# TestBoard2.net
KiCad netlist of a schematic drawn in EAGLE
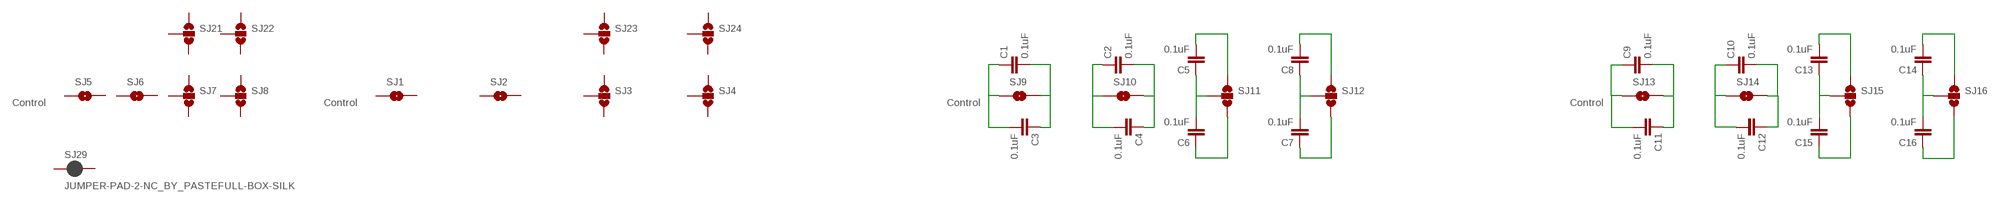
[diagram p0: schematic, sheet 1, part 1 of 3]
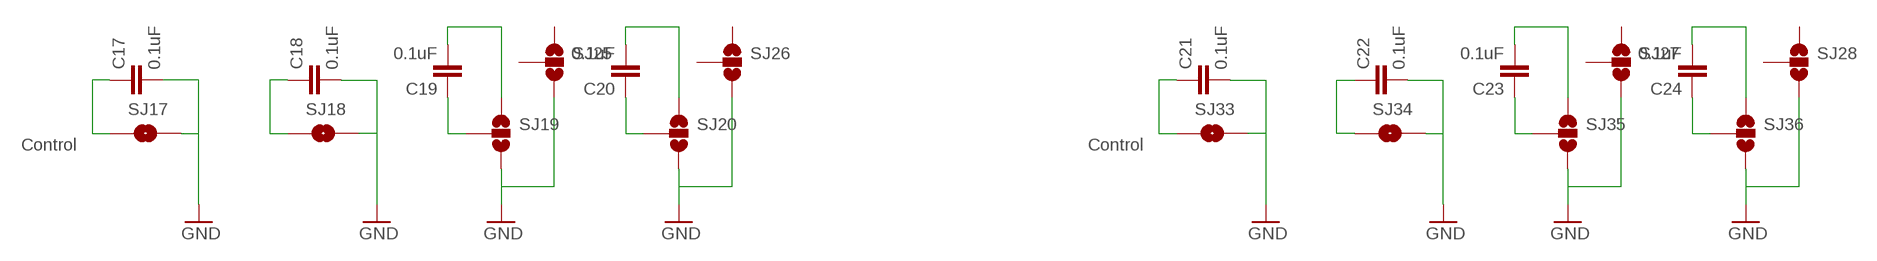
[diagram p1: schematic, sheet 1, part 2 of 3]
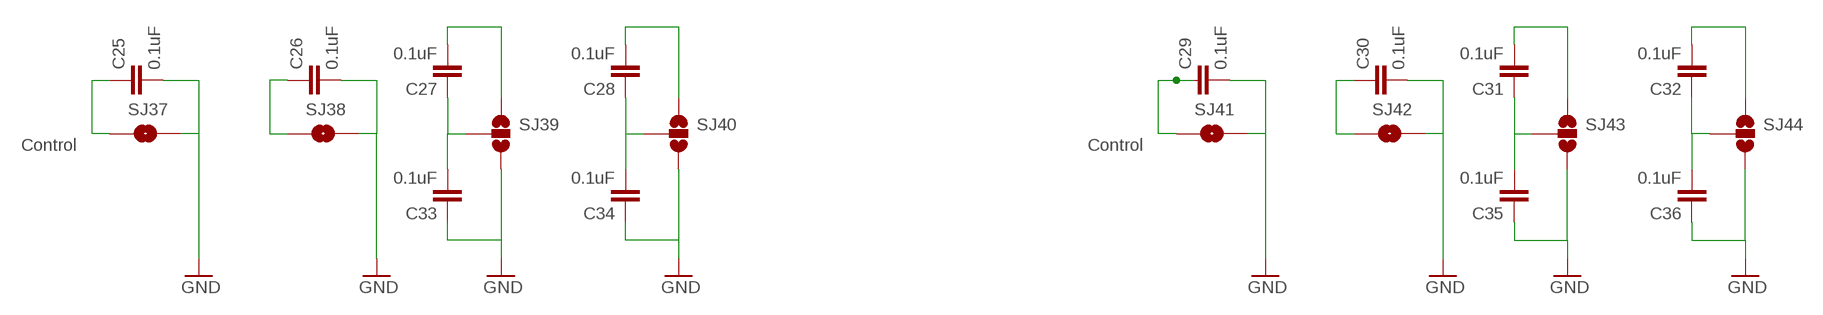
[diagram p2: schematic, sheet 1, part 3 of 3]

(export (version "E")
  (design (tool "Eeschema 10.0.6"))
  (components
    (comp (ref "C1")
      (value "0.1uF")
      (footprint "eagle-import:0603-CAP")
      (libsource (lib "eagle-import") (part "0.1UF-25V-5%(0603)"))
    )
    (comp (ref "C2")
      (value "0.1uF")
      (footprint "eagle-import:0603-CAP")
      (libsource (lib "eagle-import") (part "0.1UF-25V-5%(0603)"))
    )
    (comp (ref "C3")
      (value "0.1uF")
      (footprint "eagle-import:0603-CAP")
      (libsource (lib "eagle-import") (part "0.1UF-25V-5%(0603)"))
    )
    (comp (ref "C4")
      (value "0.1uF")
      (footprint "eagle-import:0603-CAP")
      (libsource (lib "eagle-import") (part "0.1UF-25V-5%(0603)"))
    )
    (comp (ref "C5")
      (value "0.1uF")
      (footprint "eagle-import:0603-CAP")
      (libsource (lib "eagle-import") (part "0.1UF-25V-5%(0603)"))
    )
    (comp (ref "C6")
      (value "0.1uF")
      (footprint "eagle-import:0603-CAP")
      (libsource (lib "eagle-import") (part "0.1UF-25V-5%(0603)"))
    )
    (comp (ref "C7")
      (value "0.1uF")
      (footprint "eagle-import:0603-CAP")
      (libsource (lib "eagle-import") (part "0.1UF-25V-5%(0603)"))
    )
    (comp (ref "C8")
      (value "0.1uF")
      (footprint "eagle-import:0603-CAP")
      (libsource (lib "eagle-import") (part "0.1UF-25V-5%(0603)"))
    )
    (comp (ref "C9")
      (value "0.1uF")
      (footprint "eagle-import:0603-CAP")
      (libsource (lib "eagle-import") (part "0.1UF-25V-5%(0603)"))
    )
    (comp (ref "C10")
      (value "0.1uF")
      (footprint "eagle-import:0603-CAP")
      (libsource (lib "eagle-import") (part "0.1UF-25V-5%(0603)"))
    )
    (comp (ref "C11")
      (value "0.1uF")
      (footprint "eagle-import:0603-CAP")
      (libsource (lib "eagle-import") (part "0.1UF-25V-5%(0603)"))
    )
    (comp (ref "C12")
      (value "0.1uF")
      (footprint "eagle-import:0603-CAP")
      (libsource (lib "eagle-import") (part "0.1UF-25V-5%(0603)"))
    )
    (comp (ref "C13")
      (value "0.1uF")
      (footprint "eagle-import:0603-CAP")
      (libsource (lib "eagle-import") (part "0.1UF-25V-5%(0603)"))
    )
    (comp (ref "C14")
      (value "0.1uF")
      (footprint "eagle-import:0603-CAP")
      (libsource (lib "eagle-import") (part "0.1UF-25V-5%(0603)"))
    )
    (comp (ref "C15")
      (value "0.1uF")
      (footprint "eagle-import:0603-CAP")
      (libsource (lib "eagle-import") (part "0.1UF-25V-5%(0603)"))
    )
    (comp (ref "C16")
      (value "0.1uF")
      (footprint "eagle-import:0603-CAP")
      (libsource (lib "eagle-import") (part "0.1UF-25V-5%(0603)"))
    )
    (comp (ref "C17")
      (value "0.1uF")
      (footprint "eagle-import:0603-CAP")
      (libsource (lib "eagle-import") (part "0.1UF-25V-5%(0603)"))
    )
    (comp (ref "C18")
      (value "0.1uF")
      (footprint "eagle-import:0603-CAP")
      (libsource (lib "eagle-import") (part "0.1UF-25V-5%(0603)"))
    )
    (comp (ref "C19")
      (value "0.1uF")
      (footprint "eagle-import:0603-CAP")
      (libsource (lib "eagle-import") (part "0.1UF-25V-5%(0603)"))
    )
    (comp (ref "C20")
      (value "0.1uF")
      (footprint "eagle-import:0603-CAP")
      (libsource (lib "eagle-import") (part "0.1UF-25V-5%(0603)"))
    )
    (comp (ref "C21")
      (value "0.1uF")
      (footprint "eagle-import:0603-CAP")
      (libsource (lib "eagle-import") (part "0.1UF-25V-5%(0603)"))
    )
    (comp (ref "C22")
      (value "0.1uF")
      (footprint "eagle-import:0603-CAP")
      (libsource (lib "eagle-import") (part "0.1UF-25V-5%(0603)"))
    )
    (comp (ref "C23")
      (value "0.1uF")
      (footprint "eagle-import:0603-CAP")
      (libsource (lib "eagle-import") (part "0.1UF-25V-5%(0603)"))
    )
    (comp (ref "C24")
      (value "0.1uF")
      (footprint "eagle-import:0603-CAP")
      (libsource (lib "eagle-import") (part "0.1UF-25V-5%(0603)"))
    )
    (comp (ref "C25")
      (value "0.1uF")
      (footprint "eagle-import:0603-CAP")
      (libsource (lib "eagle-import") (part "0.1UF-25V-5%(0603)"))
    )
    (comp (ref "C26")
      (value "0.1uF")
      (footprint "eagle-import:0603-CAP")
      (libsource (lib "eagle-import") (part "0.1UF-25V-5%(0603)"))
    )
    (comp (ref "C27")
      (value "0.1uF")
      (footprint "eagle-import:0603-CAP")
      (libsource (lib "eagle-import") (part "0.1UF-25V-5%(0603)"))
    )
    (comp (ref "C28")
      (value "0.1uF")
      (footprint "eagle-import:0603-CAP")
      (libsource (lib "eagle-import") (part "0.1UF-25V-5%(0603)"))
    )
    (comp (ref "C29")
      (value "0.1uF")
      (footprint "eagle-import:0603-CAP")
      (libsource (lib "eagle-import") (part "0.1UF-25V-5%(0603)"))
    )
    (comp (ref "C30")
      (value "0.1uF")
      (footprint "eagle-import:0603-CAP")
      (libsource (lib "eagle-import") (part "0.1UF-25V-5%(0603)"))
    )
    (comp (ref "C31")
      (value "0.1uF")
      (footprint "eagle-import:0603-CAP")
      (libsource (lib "eagle-import") (part "0.1UF-25V-5%(0603)"))
    )
    (comp (ref "C32")
      (value "0.1uF")
      (footprint "eagle-import:0603-CAP")
      (libsource (lib "eagle-import") (part "0.1UF-25V-5%(0603)"))
    )
    (comp (ref "C33")
      (value "0.1uF")
      (footprint "eagle-import:0603-CAP")
      (libsource (lib "eagle-import") (part "0.1UF-25V-5%(0603)"))
    )
    (comp (ref "C34")
      (value "0.1uF")
      (footprint "eagle-import:0603-CAP")
      (libsource (lib "eagle-import") (part "0.1UF-25V-5%(0603)"))
    )
    (comp (ref "C35")
      (value "0.1uF")
      (footprint "eagle-import:0603-CAP")
      (libsource (lib "eagle-import") (part "0.1UF-25V-5%(0603)"))
    )
    (comp (ref "C36")
      (value "0.1uF")
      (footprint "eagle-import:0603-CAP")
      (libsource (lib "eagle-import") (part "0.1UF-25V-5%(0603)"))
    )
    (comp (ref "SJ1")
      (value "JUMPER-PAD-2-NO")
      (footprint "eagle-import:PAD-JUMPER-2-NO_NO_SILK")
      (libsource (lib "eagle-import") (part "JUMPER-PAD-2-NO"))
    )
    (comp (ref "SJ2")
      (value "JUMPER-PAD-2-NO")
      (footprint "eagle-import:PAD-JUMPER-2-NO_NO_SILK")
      (libsource (lib "eagle-import") (part "JUMPER-PAD-2-NO"))
    )
    (comp (ref "SJ3")
      (value "JUMPER-PAD-3-NOYES_SILK")
      (footprint "eagle-import:PAD-JUMPER-3-NO_YES_SILK")
      (libsource (lib "eagle-import") (part "JUMPER-PAD-3-NOYES_SILK"))
    )
    (comp (ref "SJ4")
      (value "JUMPER-PAD-3-NOYES_SILK")
      (footprint "eagle-import:PAD-JUMPER-3-NO_YES_SILK")
      (libsource (lib "eagle-import") (part "JUMPER-PAD-3-NOYES_SILK"))
    )
    (comp (ref "SJ5")
      (value "JUMPER-PAD-2-NO")
      (footprint "eagle-import:PAD-JUMPER-2-NO_NO_SILK")
      (libsource (lib "eagle-import") (part "JUMPER-PAD-2-NO"))
    )
    (comp (ref "SJ6")
      (value "JUMPER-PAD-2-NO")
      (footprint "eagle-import:PAD-JUMPER-2-NO_NO_SILK")
      (libsource (lib "eagle-import") (part "JUMPER-PAD-2-NO"))
    )
    (comp (ref "SJ7")
      (value "JUMPER-PAD-3-NOYES_SILK")
      (footprint "eagle-import:PAD-JUMPER-3-NO_YES_SILK")
      (libsource (lib "eagle-import") (part "JUMPER-PAD-3-NOYES_SILK"))
    )
    (comp (ref "SJ8")
      (value "JUMPER-PAD-3-NOYES_SILK")
      (footprint "eagle-import:PAD-JUMPER-3-NO_YES_SILK")
      (libsource (lib "eagle-import") (part "JUMPER-PAD-3-NOYES_SILK"))
    )
    (comp (ref "SJ9")
      (value "JUMPER-PAD-2-NO")
      (footprint "eagle-import:PAD-JUMPER-2-NO_NO_SILK")
      (libsource (lib "eagle-import") (part "JUMPER-PAD-2-NO"))
    )
    (comp (ref "SJ10")
      (value "JUMPER-PAD-2-NO")
      (footprint "eagle-import:PAD-JUMPER-2-NO_NO_SILK")
      (libsource (lib "eagle-import") (part "JUMPER-PAD-2-NO"))
    )
    (comp (ref "SJ11")
      (value "JUMPER-PAD-3-NOYES_SILK")
      (footprint "eagle-import:PAD-JUMPER-3-NO_YES_SILK")
      (libsource (lib "eagle-import") (part "JUMPER-PAD-3-NOYES_SILK"))
    )
    (comp (ref "SJ12")
      (value "JUMPER-PAD-3-NOYES_SILK")
      (footprint "eagle-import:PAD-JUMPER-3-NO_YES_SILK")
      (libsource (lib "eagle-import") (part "JUMPER-PAD-3-NOYES_SILK"))
    )
    (comp (ref "SJ13")
      (value "JUMPER-PAD-2-NO")
      (footprint "eagle-import:PAD-JUMPER-2-NO_NO_SILK")
      (libsource (lib "eagle-import") (part "JUMPER-PAD-2-NO"))
    )
    (comp (ref "SJ14")
      (value "JUMPER-PAD-2-NO")
      (footprint "eagle-import:PAD-JUMPER-2-NO_NO_SILK")
      (libsource (lib "eagle-import") (part "JUMPER-PAD-2-NO"))
    )
    (comp (ref "SJ15")
      (value "JUMPER-PAD-3-NOYES_SILK")
      (footprint "eagle-import:PAD-JUMPER-3-NO_YES_SILK")
      (libsource (lib "eagle-import") (part "JUMPER-PAD-3-NOYES_SILK"))
    )
    (comp (ref "SJ16")
      (value "JUMPER-PAD-3-NOYES_SILK")
      (footprint "eagle-import:PAD-JUMPER-3-NO_YES_SILK")
      (libsource (lib "eagle-import") (part "JUMPER-PAD-3-NOYES_SILK"))
    )
    (comp (ref "SJ17")
      (value "JUMPER-PAD-2-NO")
      (footprint "eagle-import:PAD-JUMPER-2-NO_NO_SILK")
      (libsource (lib "eagle-import") (part "JUMPER-PAD-2-NO"))
    )
    (comp (ref "SJ18")
      (value "JUMPER-PAD-2-NO")
      (footprint "eagle-import:PAD-JUMPER-2-NO_NO_SILK")
      (libsource (lib "eagle-import") (part "JUMPER-PAD-2-NO"))
    )
    (comp (ref "SJ19")
      (value "JUMPER-PAD-3-NOYES_SILK")
      (footprint "eagle-import:PAD-JUMPER-3-NO_YES_SILK")
      (libsource (lib "eagle-import") (part "JUMPER-PAD-3-NOYES_SILK"))
    )
    (comp (ref "SJ20")
      (value "JUMPER-PAD-3-NOYES_SILK")
      (footprint "eagle-import:PAD-JUMPER-3-NO_YES_SILK")
      (libsource (lib "eagle-import") (part "JUMPER-PAD-3-NOYES_SILK"))
    )
    (comp (ref "SJ21")
      (value "JUMPER-PAD-3-NOYES_SILK")
      (footprint "eagle-import:PAD-JUMPER-3-NO_YES_SILK")
      (libsource (lib "eagle-import") (part "JUMPER-PAD-3-NOYES_SILK"))
    )
    (comp (ref "SJ22")
      (value "JUMPER-PAD-3-NOYES_SILK")
      (footprint "eagle-import:PAD-JUMPER-3-NO_YES_SILK")
      (libsource (lib "eagle-import") (part "JUMPER-PAD-3-NOYES_SILK"))
    )
    (comp (ref "SJ23")
      (value "JUMPER-PAD-3-NOYES_SILK")
      (footprint "eagle-import:PAD-JUMPER-3-NO_YES_SILK")
      (libsource (lib "eagle-import") (part "JUMPER-PAD-3-NOYES_SILK"))
    )
    (comp (ref "SJ24")
      (value "JUMPER-PAD-3-NOYES_SILK")
      (footprint "eagle-import:PAD-JUMPER-3-NO_YES_SILK")
      (libsource (lib "eagle-import") (part "JUMPER-PAD-3-NOYES_SILK"))
    )
    (comp (ref "SJ25")
      (value "JUMPER-PAD-3-NOYES_SILK")
      (footprint "eagle-import:PAD-JUMPER-3-NO_YES_SILK")
      (libsource (lib "eagle-import") (part "JUMPER-PAD-3-NOYES_SILK"))
    )
    (comp (ref "SJ26")
      (value "JUMPER-PAD-3-NOYES_SILK")
      (footprint "eagle-import:PAD-JUMPER-3-NO_YES_SILK")
      (libsource (lib "eagle-import") (part "JUMPER-PAD-3-NOYES_SILK"))
    )
    (comp (ref "SJ27")
      (value "JUMPER-PAD-3-NOYES_SILK")
      (footprint "eagle-import:PAD-JUMPER-3-NO_YES_SILK")
      (libsource (lib "eagle-import") (part "JUMPER-PAD-3-NOYES_SILK"))
    )
    (comp (ref "SJ28")
      (value "JUMPER-PAD-3-NOYES_SILK")
      (footprint "eagle-import:PAD-JUMPER-3-NO_YES_SILK")
      (libsource (lib "eagle-import") (part "JUMPER-PAD-3-NOYES_SILK"))
    )
    (comp (ref "SJ29")
      (value "JUMPER-PAD-2-NC_BY_PASTEFULL-BOX-SILK")
      (footprint "eagle-import:PAD-JUMPER-2-NC_BY_PASTE_YES_SILK_FULL_BOX")
      (libsource (lib "eagle-import") (part "JUMPER-PAD-2-NC_BY_PASTEFULL-BOX-SILK"))
    )
    (comp (ref "SJ33")
      (value "JUMPER-PAD-2-NO")
      (footprint "eagle-import:PAD-JUMPER-2-NO_NO_SILK")
      (libsource (lib "eagle-import") (part "JUMPER-PAD-2-NO"))
    )
    (comp (ref "SJ34")
      (value "JUMPER-PAD-2-NO")
      (footprint "eagle-import:PAD-JUMPER-2-NO_NO_SILK")
      (libsource (lib "eagle-import") (part "JUMPER-PAD-2-NO"))
    )
    (comp (ref "SJ35")
      (value "JUMPER-PAD-3-NOYES_SILK")
      (footprint "eagle-import:PAD-JUMPER-3-NO_YES_SILK")
      (libsource (lib "eagle-import") (part "JUMPER-PAD-3-NOYES_SILK"))
    )
    (comp (ref "SJ36")
      (value "JUMPER-PAD-3-NOYES_SILK")
      (footprint "eagle-import:PAD-JUMPER-3-NO_YES_SILK")
      (libsource (lib "eagle-import") (part "JUMPER-PAD-3-NOYES_SILK"))
    )
    (comp (ref "SJ37")
      (value "JUMPER-PAD-2-NO")
      (footprint "eagle-import:PAD-JUMPER-2-NO_NO_SILK")
      (libsource (lib "eagle-import") (part "JUMPER-PAD-2-NO"))
    )
    (comp (ref "SJ38")
      (value "JUMPER-PAD-2-NO")
      (footprint "eagle-import:PAD-JUMPER-2-NO_NO_SILK")
      (libsource (lib "eagle-import") (part "JUMPER-PAD-2-NO"))
    )
    (comp (ref "SJ39")
      (value "JUMPER-PAD-3-NOYES_SILK")
      (footprint "eagle-import:PAD-JUMPER-3-NO_YES_SILK")
      (libsource (lib "eagle-import") (part "JUMPER-PAD-3-NOYES_SILK"))
    )
    (comp (ref "SJ40")
      (value "JUMPER-PAD-3-NOYES_SILK")
      (footprint "eagle-import:PAD-JUMPER-3-NO_YES_SILK")
      (libsource (lib "eagle-import") (part "JUMPER-PAD-3-NOYES_SILK"))
    )
    (comp (ref "SJ41")
      (value "JUMPER-PAD-2-NO")
      (footprint "eagle-import:PAD-JUMPER-2-NO_NO_SILK")
      (libsource (lib "eagle-import") (part "JUMPER-PAD-2-NO"))
    )
    (comp (ref "SJ42")
      (value "JUMPER-PAD-2-NO")
      (footprint "eagle-import:PAD-JUMPER-2-NO_NO_SILK")
      (libsource (lib "eagle-import") (part "JUMPER-PAD-2-NO"))
    )
    (comp (ref "SJ43")
      (value "JUMPER-PAD-3-NOYES_SILK")
      (footprint "eagle-import:PAD-JUMPER-3-NO_YES_SILK")
      (libsource (lib "eagle-import") (part "JUMPER-PAD-3-NOYES_SILK"))
    )
    (comp (ref "SJ44")
      (value "JUMPER-PAD-3-NOYES_SILK")
      (footprint "eagle-import:PAD-JUMPER-3-NO_YES_SILK")
      (libsource (lib "eagle-import") (part "JUMPER-PAD-3-NOYES_SILK"))
    )
  )
  (nets
    (net (code "1") (name "GND") (class "Default")
      (node (ref "C17") (pin "2") (pinfunction "2_2") (pintype "passive"))
      (node (ref "C18") (pin "2") (pinfunction "2_2") (pintype "passive"))
      (node (ref "C21") (pin "2") (pinfunction "2_2") (pintype "passive"))
      (node (ref "C22") (pin "2") (pinfunction "2_2") (pintype "passive"))
      (node (ref "C25") (pin "2") (pinfunction "2_2") (pintype "passive"))
      (node (ref "C26") (pin "2") (pinfunction "2_2") (pintype "passive"))
      (node (ref "C29") (pin "2") (pinfunction "2_2") (pintype "passive"))
      (node (ref "C30") (pin "2") (pinfunction "2_2") (pintype "passive"))
      (node (ref "C33") (pin "1") (pinfunction "1_1") (pintype "passive"))
      (node (ref "C34") (pin "1") (pinfunction "1_1") (pintype "passive"))
      (node (ref "C35") (pin "1") (pinfunction "1_1") (pintype "passive"))
      (node (ref "C36") (pin "1") (pinfunction "1_1") (pintype "passive"))
      (node (ref "SJ17") (pin "2") (pinfunction "2_2") (pintype "passive"))
      (node (ref "SJ18") (pin "2") (pinfunction "2_2") (pintype "passive"))
      (node (ref "SJ19") (pin "3") (pinfunction "3_3") (pintype "passive"))
      (node (ref "SJ20") (pin "3") (pinfunction "3_3") (pintype "passive"))
      (node (ref "SJ25") (pin "3") (pinfunction "3_3") (pintype "passive"))
      (node (ref "SJ26") (pin "3") (pinfunction "3_3") (pintype "passive"))
      (node (ref "SJ27") (pin "3") (pinfunction "3_3") (pintype "passive"))
      (node (ref "SJ28") (pin "3") (pinfunction "3_3") (pintype "passive"))
      (node (ref "SJ33") (pin "2") (pinfunction "2_2") (pintype "passive"))
      (node (ref "SJ34") (pin "2") (pinfunction "2_2") (pintype "passive"))
      (node (ref "SJ35") (pin "3") (pinfunction "3_3") (pintype "passive"))
      (node (ref "SJ36") (pin "3") (pinfunction "3_3") (pintype "passive"))
      (node (ref "SJ37") (pin "2") (pinfunction "2_2") (pintype "passive"))
      (node (ref "SJ38") (pin "2") (pinfunction "2_2") (pintype "passive"))
      (node (ref "SJ39") (pin "3") (pinfunction "3_3") (pintype "passive"))
      (node (ref "SJ40") (pin "3") (pinfunction "3_3") (pintype "passive"))
      (node (ref "SJ41") (pin "2") (pinfunction "2_2") (pintype "passive"))
      (node (ref "SJ42") (pin "2") (pinfunction "2_2") (pintype "passive"))
      (node (ref "SJ43") (pin "3") (pinfunction "3_3") (pintype "passive"))
      (node (ref "SJ44") (pin "3") (pinfunction "3_3") (pintype "passive"))
    )
    (net (code "2") (name "Net-(C1-Pad1)") (class "Default")
      (node (ref "C1") (pin "1") (pinfunction "1_1") (pintype "passive"))
      (node (ref "C3") (pin "2") (pinfunction "2_2") (pintype "passive"))
      (node (ref "SJ9") (pin "1") (pinfunction "1_1") (pintype "passive"))
    )
    (net (code "3") (name "Net-(C1-Pad2)") (class "Default")
      (node (ref "C1") (pin "2") (pinfunction "2_2") (pintype "passive"))
      (node (ref "C3") (pin "1") (pinfunction "1_1") (pintype "passive"))
      (node (ref "SJ9") (pin "2") (pinfunction "2_2") (pintype "passive"))
    )
    (net (code "4") (name "Net-(C2-Pad1)") (class "Default")
      (node (ref "C2") (pin "1") (pinfunction "1_1") (pintype "passive"))
      (node (ref "C4") (pin "2") (pinfunction "2_2") (pintype "passive"))
      (node (ref "SJ10") (pin "1") (pinfunction "1_1") (pintype "passive"))
    )
    (net (code "5") (name "Net-(C2-Pad2)") (class "Default")
      (node (ref "C2") (pin "2") (pinfunction "2_2") (pintype "passive"))
      (node (ref "C4") (pin "1") (pinfunction "1_1") (pintype "passive"))
      (node (ref "SJ10") (pin "2") (pinfunction "2_2") (pintype "passive"))
    )
    (net (code "6") (name "Net-(C5-Pad1)") (class "Default")
      (node (ref "C5") (pin "1") (pinfunction "1_1") (pintype "passive"))
      (node (ref "C6") (pin "2") (pinfunction "2_2") (pintype "passive"))
      (node (ref "SJ11") (pin "2") (pinfunction "2_2") (pintype "passive"))
    )
    (net (code "7") (name "Net-(C5-Pad2)") (class "Default")
      (node (ref "C5") (pin "2") (pinfunction "2_2") (pintype "passive"))
      (node (ref "SJ11") (pin "1") (pinfunction "1_1") (pintype "passive"))
    )
    (net (code "8") (name "Net-(C6-Pad1)") (class "Default")
      (node (ref "C6") (pin "1") (pinfunction "1_1") (pintype "passive"))
      (node (ref "SJ11") (pin "3") (pinfunction "3_3") (pintype "passive"))
    )
    (net (code "9") (name "Net-(C7-Pad1)") (class "Default")
      (node (ref "C7") (pin "1") (pinfunction "1_1") (pintype "passive"))
      (node (ref "SJ12") (pin "3") (pinfunction "3_3") (pintype "passive"))
    )
    (net (code "10") (name "Net-(C7-Pad2)") (class "Default")
      (node (ref "C7") (pin "2") (pinfunction "2_2") (pintype "passive"))
      (node (ref "C8") (pin "1") (pinfunction "1_1") (pintype "passive"))
      (node (ref "SJ12") (pin "2") (pinfunction "2_2") (pintype "passive"))
    )
    (net (code "11") (name "Net-(C8-Pad2)") (class "Default")
      (node (ref "C8") (pin "2") (pinfunction "2_2") (pintype "passive"))
      (node (ref "SJ12") (pin "1") (pinfunction "1_1") (pintype "passive"))
    )
    (net (code "12") (name "Net-(C10-Pad1)") (class "Default")
      (node (ref "C10") (pin "1") (pinfunction "1_1") (pintype "passive"))
      (node (ref "C12") (pin "2") (pinfunction "2_2") (pintype "passive"))
      (node (ref "SJ14") (pin "1") (pinfunction "1_1") (pintype "passive"))
    )
    (net (code "13") (name "Net-(C10-Pad2)") (class "Default")
      (node (ref "C10") (pin "2") (pinfunction "2_2") (pintype "passive"))
      (node (ref "C12") (pin "1") (pinfunction "1_1") (pintype "passive"))
      (node (ref "SJ14") (pin "2") (pinfunction "2_2") (pintype "passive"))
    )
    (net (code "14") (name "Net-(C11-Pad1)") (class "Default")
      (node (ref "C11") (pin "1") (pinfunction "1_1") (pintype "passive"))
      (node (ref "C9") (pin "2") (pinfunction "2_2") (pintype "passive"))
      (node (ref "SJ13") (pin "2") (pinfunction "2_2") (pintype "passive"))
    )
    (net (code "15") (name "Net-(C11-Pad2)") (class "Default")
      (node (ref "C11") (pin "2") (pinfunction "2_2") (pintype "passive"))
      (node (ref "C9") (pin "1") (pinfunction "1_1") (pintype "passive"))
      (node (ref "SJ13") (pin "1") (pinfunction "1_1") (pintype "passive"))
    )
    (net (code "16") (name "Net-(C13-Pad1)") (class "Default")
      (node (ref "C13") (pin "1") (pinfunction "1_1") (pintype "passive"))
      (node (ref "C15") (pin "2") (pinfunction "2_2") (pintype "passive"))
      (node (ref "SJ15") (pin "2") (pinfunction "2_2") (pintype "passive"))
    )
    (net (code "17") (name "Net-(C13-Pad2)") (class "Default")
      (node (ref "C13") (pin "2") (pinfunction "2_2") (pintype "passive"))
      (node (ref "SJ15") (pin "1") (pinfunction "1_1") (pintype "passive"))
    )
    (net (code "18") (name "Net-(C14-Pad1)") (class "Default")
      (node (ref "C14") (pin "1") (pinfunction "1_1") (pintype "passive"))
      (node (ref "C16") (pin "2") (pinfunction "2_2") (pintype "passive"))
      (node (ref "SJ16") (pin "2") (pinfunction "2_2") (pintype "passive"))
    )
    (net (code "19") (name "Net-(C14-Pad2)") (class "Default")
      (node (ref "C14") (pin "2") (pinfunction "2_2") (pintype "passive"))
      (node (ref "SJ16") (pin "1") (pinfunction "1_1") (pintype "passive"))
    )
    (net (code "20") (name "Net-(C15-Pad1)") (class "Default")
      (node (ref "C15") (pin "1") (pinfunction "1_1") (pintype "passive"))
      (node (ref "SJ15") (pin "3") (pinfunction "3_3") (pintype "passive"))
    )
    (net (code "21") (name "Net-(C16-Pad1)") (class "Default")
      (node (ref "C16") (pin "1") (pinfunction "1_1") (pintype "passive"))
      (node (ref "SJ16") (pin "3") (pinfunction "3_3") (pintype "passive"))
    )
    (net (code "22") (name "Net-(C17-Pad1)") (class "Default")
      (node (ref "C17") (pin "1") (pinfunction "1_1") (pintype "passive"))
      (node (ref "SJ17") (pin "1") (pinfunction "1_1") (pintype "passive"))
    )
    (net (code "23") (name "Net-(C18-Pad1)") (class "Default")
      (node (ref "C18") (pin "1") (pinfunction "1_1") (pintype "passive"))
      (node (ref "SJ18") (pin "1") (pinfunction "1_1") (pintype "passive"))
    )
    (net (code "24") (name "Net-(C19-Pad1)") (class "Default")
      (node (ref "C19") (pin "1") (pinfunction "1_1") (pintype "passive"))
      (node (ref "SJ19") (pin "2") (pinfunction "2_2") (pintype "passive"))
    )
    (net (code "25") (name "Net-(C19-Pad2)") (class "Default")
      (node (ref "C19") (pin "2") (pinfunction "2_2") (pintype "passive"))
      (node (ref "SJ19") (pin "1") (pinfunction "1_1") (pintype "passive"))
    )
    (net (code "26") (name "Net-(C20-Pad1)") (class "Default")
      (node (ref "C20") (pin "1") (pinfunction "1_1") (pintype "passive"))
      (node (ref "SJ20") (pin "2") (pinfunction "2_2") (pintype "passive"))
    )
    (net (code "27") (name "Net-(C20-Pad2)") (class "Default")
      (node (ref "C20") (pin "2") (pinfunction "2_2") (pintype "passive"))
      (node (ref "SJ20") (pin "1") (pinfunction "1_1") (pintype "passive"))
    )
    (net (code "28") (name "Net-(C21-Pad1)") (class "Default")
      (node (ref "C21") (pin "1") (pinfunction "1_1") (pintype "passive"))
      (node (ref "SJ33") (pin "1") (pinfunction "1_1") (pintype "passive"))
    )
    (net (code "29") (name "Net-(C22-Pad1)") (class "Default")
      (node (ref "C22") (pin "1") (pinfunction "1_1") (pintype "passive"))
      (node (ref "SJ34") (pin "1") (pinfunction "1_1") (pintype "passive"))
    )
    (net (code "30") (name "Net-(C23-Pad1)") (class "Default")
      (node (ref "C23") (pin "1") (pinfunction "1_1") (pintype "passive"))
      (node (ref "SJ35") (pin "2") (pinfunction "2_2") (pintype "passive"))
    )
    (net (code "31") (name "Net-(C23-Pad2)") (class "Default")
      (node (ref "C23") (pin "2") (pinfunction "2_2") (pintype "passive"))
      (node (ref "SJ35") (pin "1") (pinfunction "1_1") (pintype "passive"))
    )
    (net (code "32") (name "Net-(C24-Pad1)") (class "Default")
      (node (ref "C24") (pin "1") (pinfunction "1_1") (pintype "passive"))
      (node (ref "SJ36") (pin "2") (pinfunction "2_2") (pintype "passive"))
    )
    (net (code "33") (name "Net-(C24-Pad2)") (class "Default")
      (node (ref "C24") (pin "2") (pinfunction "2_2") (pintype "passive"))
      (node (ref "SJ36") (pin "1") (pinfunction "1_1") (pintype "passive"))
    )
    (net (code "34") (name "Net-(C25-Pad1)") (class "Default")
      (node (ref "C25") (pin "1") (pinfunction "1_1") (pintype "passive"))
      (node (ref "SJ37") (pin "1") (pinfunction "1_1") (pintype "passive"))
    )
    (net (code "35") (name "Net-(C26-Pad1)") (class "Default")
      (node (ref "C26") (pin "1") (pinfunction "1_1") (pintype "passive"))
      (node (ref "SJ38") (pin "1") (pinfunction "1_1") (pintype "passive"))
    )
    (net (code "36") (name "Net-(C27-Pad1)") (class "Default")
      (node (ref "C27") (pin "1") (pinfunction "1_1") (pintype "passive"))
      (node (ref "C33") (pin "2") (pinfunction "2_2") (pintype "passive"))
      (node (ref "SJ39") (pin "2") (pinfunction "2_2") (pintype "passive"))
    )
    (net (code "37") (name "Net-(C27-Pad2)") (class "Default")
      (node (ref "C27") (pin "2") (pinfunction "2_2") (pintype "passive"))
      (node (ref "SJ39") (pin "1") (pinfunction "1_1") (pintype "passive"))
    )
    (net (code "38") (name "Net-(C28-Pad1)") (class "Default")
      (node (ref "C28") (pin "1") (pinfunction "1_1") (pintype "passive"))
      (node (ref "C34") (pin "2") (pinfunction "2_2") (pintype "passive"))
      (node (ref "SJ40") (pin "2") (pinfunction "2_2") (pintype "passive"))
    )
    (net (code "39") (name "Net-(C28-Pad2)") (class "Default")
      (node (ref "C28") (pin "2") (pinfunction "2_2") (pintype "passive"))
      (node (ref "SJ40") (pin "1") (pinfunction "1_1") (pintype "passive"))
    )
    (net (code "40") (name "Net-(C29-Pad1)") (class "Default")
      (node (ref "C29") (pin "1") (pinfunction "1_1") (pintype "passive"))
      (node (ref "SJ41") (pin "1") (pinfunction "1_1") (pintype "passive"))
    )
    (net (code "41") (name "Net-(C30-Pad1)") (class "Default")
      (node (ref "C30") (pin "1") (pinfunction "1_1") (pintype "passive"))
      (node (ref "SJ42") (pin "1") (pinfunction "1_1") (pintype "passive"))
    )
    (net (code "42") (name "Net-(C31-Pad1)") (class "Default")
      (node (ref "C31") (pin "1") (pinfunction "1_1") (pintype "passive"))
      (node (ref "C35") (pin "2") (pinfunction "2_2") (pintype "passive"))
      (node (ref "SJ43") (pin "2") (pinfunction "2_2") (pintype "passive"))
    )
    (net (code "43") (name "Net-(C31-Pad2)") (class "Default")
      (node (ref "C31") (pin "2") (pinfunction "2_2") (pintype "passive"))
      (node (ref "SJ43") (pin "1") (pinfunction "1_1") (pintype "passive"))
    )
    (net (code "44") (name "Net-(C32-Pad1)") (class "Default")
      (node (ref "C32") (pin "1") (pinfunction "1_1") (pintype "passive"))
      (node (ref "C36") (pin "2") (pinfunction "2_2") (pintype "passive"))
      (node (ref "SJ44") (pin "2") (pinfunction "2_2") (pintype "passive"))
    )
    (net (code "45") (name "Net-(C32-Pad2)") (class "Default")
      (node (ref "C32") (pin "2") (pinfunction "2_2") (pintype "passive"))
      (node (ref "SJ44") (pin "1") (pinfunction "1_1") (pintype "passive"))
    )
    (net (code "46") (name "unconnected-(SJ1-Pad1)") (class "Default")
      (node (ref "SJ1") (pin "1") (pinfunction "1_1") (pintype "passive"))
    )
    (net (code "47") (name "unconnected-(SJ1-Pad2)") (class "Default")
      (node (ref "SJ1") (pin "2") (pinfunction "2_2") (pintype "passive"))
    )
    (net (code "48") (name "unconnected-(SJ2-Pad1)") (class "Default")
      (node (ref "SJ2") (pin "1") (pinfunction "1_1") (pintype "passive"))
    )
    (net (code "49") (name "unconnected-(SJ2-Pad2)") (class "Default")
      (node (ref "SJ2") (pin "2") (pinfunction "2_2") (pintype "passive"))
    )
    (net (code "50") (name "unconnected-(SJ3-Pad1)") (class "Default")
      (node (ref "SJ3") (pin "1") (pinfunction "1_1") (pintype "passive"))
    )
    (net (code "51") (name "unconnected-(SJ3-Pad2)") (class "Default")
      (node (ref "SJ3") (pin "2") (pinfunction "2_2") (pintype "passive"))
    )
    (net (code "52") (name "unconnected-(SJ3-Pad3)") (class "Default")
      (node (ref "SJ3") (pin "3") (pinfunction "3_3") (pintype "passive"))
    )
    (net (code "53") (name "unconnected-(SJ4-Pad1)") (class "Default")
      (node (ref "SJ4") (pin "1") (pinfunction "1_1") (pintype "passive"))
    )
    (net (code "54") (name "unconnected-(SJ4-Pad2)") (class "Default")
      (node (ref "SJ4") (pin "2") (pinfunction "2_2") (pintype "passive"))
    )
    (net (code "55") (name "unconnected-(SJ4-Pad3)") (class "Default")
      (node (ref "SJ4") (pin "3") (pinfunction "3_3") (pintype "passive"))
    )
    (net (code "56") (name "unconnected-(SJ5-Pad1)") (class "Default")
      (node (ref "SJ5") (pin "1") (pinfunction "1_1") (pintype "passive"))
    )
    (net (code "57") (name "unconnected-(SJ5-Pad2)") (class "Default")
      (node (ref "SJ5") (pin "2") (pinfunction "2_2") (pintype "passive"))
    )
    (net (code "58") (name "unconnected-(SJ6-Pad1)") (class "Default")
      (node (ref "SJ6") (pin "1") (pinfunction "1_1") (pintype "passive"))
    )
    (net (code "59") (name "unconnected-(SJ6-Pad2)") (class "Default")
      (node (ref "SJ6") (pin "2") (pinfunction "2_2") (pintype "passive"))
    )
    (net (code "60") (name "unconnected-(SJ7-Pad1)") (class "Default")
      (node (ref "SJ7") (pin "1") (pinfunction "1_1") (pintype "passive"))
    )
    (net (code "61") (name "unconnected-(SJ7-Pad2)") (class "Default")
      (node (ref "SJ7") (pin "2") (pinfunction "2_2") (pintype "passive"))
    )
    (net (code "62") (name "unconnected-(SJ7-Pad3)") (class "Default")
      (node (ref "SJ7") (pin "3") (pinfunction "3_3") (pintype "passive"))
    )
    (net (code "63") (name "unconnected-(SJ8-Pad1)") (class "Default")
      (node (ref "SJ8") (pin "1") (pinfunction "1_1") (pintype "passive"))
    )
    (net (code "64") (name "unconnected-(SJ8-Pad2)") (class "Default")
      (node (ref "SJ8") (pin "2") (pinfunction "2_2") (pintype "passive"))
    )
    (net (code "65") (name "unconnected-(SJ8-Pad3)") (class "Default")
      (node (ref "SJ8") (pin "3") (pinfunction "3_3") (pintype "passive"))
    )
    (net (code "66") (name "unconnected-(SJ21-Pad1)") (class "Default")
      (node (ref "SJ21") (pin "1") (pinfunction "1_1") (pintype "passive"))
    )
    (net (code "67") (name "unconnected-(SJ21-Pad2)") (class "Default")
      (node (ref "SJ21") (pin "2") (pinfunction "2_2") (pintype "passive"))
    )
    (net (code "68") (name "unconnected-(SJ21-Pad3)") (class "Default")
      (node (ref "SJ21") (pin "3") (pinfunction "3_3") (pintype "passive"))
    )
    (net (code "69") (name "unconnected-(SJ22-Pad1)") (class "Default")
      (node (ref "SJ22") (pin "1") (pinfunction "1_1") (pintype "passive"))
    )
    (net (code "70") (name "unconnected-(SJ22-Pad2)") (class "Default")
      (node (ref "SJ22") (pin "2") (pinfunction "2_2") (pintype "passive"))
    )
    (net (code "71") (name "unconnected-(SJ22-Pad3)") (class "Default")
      (node (ref "SJ22") (pin "3") (pinfunction "3_3") (pintype "passive"))
    )
    (net (code "72") (name "unconnected-(SJ23-Pad1)") (class "Default")
      (node (ref "SJ23") (pin "1") (pinfunction "1_1") (pintype "passive"))
    )
    (net (code "73") (name "unconnected-(SJ23-Pad2)") (class "Default")
      (node (ref "SJ23") (pin "2") (pinfunction "2_2") (pintype "passive"))
    )
    (net (code "74") (name "unconnected-(SJ23-Pad3)") (class "Default")
      (node (ref "SJ23") (pin "3") (pinfunction "3_3") (pintype "passive"))
    )
    (net (code "75") (name "unconnected-(SJ24-Pad1)") (class "Default")
      (node (ref "SJ24") (pin "1") (pinfunction "1_1") (pintype "passive"))
    )
    (net (code "76") (name "unconnected-(SJ24-Pad2)") (class "Default")
      (node (ref "SJ24") (pin "2") (pinfunction "2_2") (pintype "passive"))
    )
    (net (code "77") (name "unconnected-(SJ24-Pad3)") (class "Default")
      (node (ref "SJ24") (pin "3") (pinfunction "3_3") (pintype "passive"))
    )
    (net (code "78") (name "unconnected-(SJ25-Pad1)") (class "Default")
      (node (ref "SJ25") (pin "1") (pinfunction "1_1") (pintype "passive"))
    )
    (net (code "79") (name "unconnected-(SJ25-Pad2)") (class "Default")
      (node (ref "SJ25") (pin "2") (pinfunction "2_2") (pintype "passive"))
    )
    (net (code "80") (name "unconnected-(SJ26-Pad1)") (class "Default")
      (node (ref "SJ26") (pin "1") (pinfunction "1_1") (pintype "passive"))
    )
    (net (code "81") (name "unconnected-(SJ26-Pad2)") (class "Default")
      (node (ref "SJ26") (pin "2") (pinfunction "2_2") (pintype "passive"))
    )
    (net (code "82") (name "unconnected-(SJ27-Pad1)") (class "Default")
      (node (ref "SJ27") (pin "1") (pinfunction "1_1") (pintype "passive"))
    )
    (net (code "83") (name "unconnected-(SJ27-Pad2)") (class "Default")
      (node (ref "SJ27") (pin "2") (pinfunction "2_2") (pintype "passive"))
    )
    (net (code "84") (name "unconnected-(SJ28-Pad1)") (class "Default")
      (node (ref "SJ28") (pin "1") (pinfunction "1_1") (pintype "passive"))
    )
    (net (code "85") (name "unconnected-(SJ28-Pad2)") (class "Default")
      (node (ref "SJ28") (pin "2") (pinfunction "2_2") (pintype "passive"))
    )
    (net (code "86") (name "unconnected-(SJ29-Pad1)") (class "Default")
      (node (ref "SJ29") (pin "1") (pinfunction "1_1") (pintype "passive"))
    )
    (net (code "87") (name "unconnected-(SJ29-Pad2)") (class "Default")
      (node (ref "SJ29") (pin "2") (pinfunction "2_2") (pintype "passive"))
    )
  )
)
